# POWER.net
KiCad netlist of a schematic drawn in Altium Designer
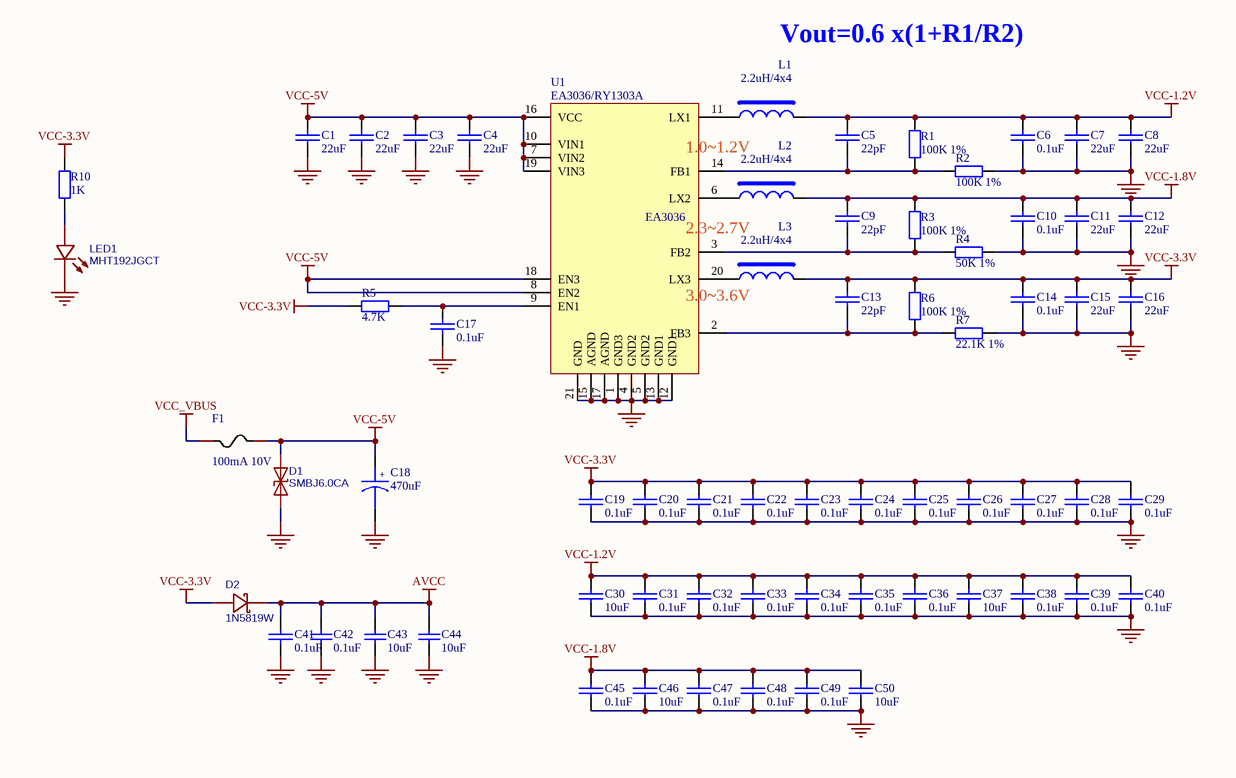
[diagram p0: POWER.SchDoc]

(export (version "E")
  (design (tool "Eeschema 10.0.6"))
  (components
    (comp (ref "C1")
      (value "22uF")
      (footprint "0805_C")
      (description "贴片电容")
      (libsource (lib "*") (part "CAP"))
    )
    (comp (ref "C2")
      (value "22uF")
      (footprint "0805_C")
      (description "贴片电容")
      (libsource (lib "*") (part "CAP"))
    )
    (comp (ref "C3")
      (value "22uF")
      (footprint "0805_C")
      (description "贴片电容")
      (libsource (lib "*") (part "CAP"))
    )
    (comp (ref "C4")
      (value "22uF")
      (footprint "0805_C")
      (description "贴片电容")
      (libsource (lib "*") (part "CAP"))
    )
    (comp (ref "C5")
      (value "22pF")
      (footprint "0402_C")
      (description "贴片电容")
      (libsource (lib "*") (part "CAP"))
    )
    (comp (ref "C6")
      (value "0.1uF")
      (footprint "0402_C")
      (description "贴片电容")
      (libsource (lib "*") (part "CAP"))
    )
    (comp (ref "C7")
      (value "22uF")
      (footprint "0805_C")
      (description "贴片电容")
      (libsource (lib "*") (part "CAP"))
    )
    (comp (ref "C8")
      (value "22uF")
      (footprint "0805_C")
      (description "贴片电容")
      (libsource (lib "*") (part "CAP"))
    )
    (comp (ref "C9")
      (value "22pF")
      (footprint "0402_C")
      (description "贴片电容")
      (libsource (lib "*") (part "CAP"))
    )
    (comp (ref "C10")
      (value "0.1uF")
      (footprint "0402_C")
      (description "贴片电容")
      (libsource (lib "*") (part "CAP"))
    )
    (comp (ref "C11")
      (value "22uF")
      (footprint "0805_C")
      (description "贴片电容")
      (libsource (lib "*") (part "CAP"))
    )
    (comp (ref "C12")
      (value "22uF")
      (footprint "0805_C")
      (description "贴片电容")
      (libsource (lib "*") (part "CAP"))
    )
    (comp (ref "C13")
      (value "22pF")
      (footprint "0402_C")
      (description "贴片电容")
      (libsource (lib "*") (part "CAP"))
    )
    (comp (ref "C14")
      (value "0.1uF")
      (footprint "0402_C")
      (description "贴片电容")
      (libsource (lib "*") (part "CAP"))
    )
    (comp (ref "C15")
      (value "22uF")
      (footprint "0805_C")
      (description "贴片电容")
      (libsource (lib "*") (part "CAP"))
    )
    (comp (ref "C16")
      (value "22uF")
      (footprint "0805_C")
      (description "贴片电容")
      (libsource (lib "*") (part "CAP"))
    )
    (comp (ref "C17")
      (value "0.1uF")
      (footprint "0402_C")
      (description "贴片电容")
      (libsource (lib "*") (part "CAP"))
    )
    (comp (ref "C18")
      (value "470uF")
      (footprint "SEC6.3")
      (description "贴片电解电容")
      (libsource (lib "*") (part "CAPACITOR POL"))
    )
    (comp (ref "C19")
      (value "0.1uF")
      (footprint "0402_C")
      (description "贴片电容")
      (libsource (lib "*") (part "CAP"))
    )
    (comp (ref "C20")
      (value "0.1uF")
      (footprint "0402_C")
      (description "贴片电容")
      (libsource (lib "*") (part "CAP"))
    )
    (comp (ref "C21")
      (value "0.1uF")
      (footprint "0402_C")
      (description "贴片电容")
      (libsource (lib "*") (part "CAP"))
    )
    (comp (ref "C22")
      (value "0.1uF")
      (footprint "0402_C")
      (description "贴片电容")
      (libsource (lib "*") (part "CAP"))
    )
    (comp (ref "C23")
      (value "0.1uF")
      (footprint "0402_C")
      (description "贴片电容")
      (libsource (lib "*") (part "CAP"))
    )
    (comp (ref "C24")
      (value "0.1uF")
      (footprint "0402_C")
      (description "贴片电容")
      (libsource (lib "*") (part "CAP"))
    )
    (comp (ref "C25")
      (value "0.1uF")
      (footprint "0402_C")
      (description "贴片电容")
      (libsource (lib "*") (part "CAP"))
    )
    (comp (ref "C26")
      (value "0.1uF")
      (footprint "0402_C")
      (description "贴片电容")
      (libsource (lib "*") (part "CAP"))
    )
    (comp (ref "C27")
      (value "0.1uF")
      (footprint "0402_C")
      (description "贴片电容")
      (libsource (lib "*") (part "CAP"))
    )
    (comp (ref "C28")
      (value "0.1uF")
      (footprint "0402_C")
      (description "贴片电容")
      (libsource (lib "*") (part "CAP"))
    )
    (comp (ref "C29")
      (value "0.1uF")
      (footprint "0402_C")
      (description "贴片电容")
      (libsource (lib "*") (part "CAP"))
    )
    (comp (ref "C30")
      (value "10uF")
      (footprint "0603_C")
      (description "贴片电容")
      (libsource (lib "*") (part "CAP"))
    )
    (comp (ref "C31")
      (value "0.1uF")
      (footprint "0402_C")
      (description "贴片电容")
      (libsource (lib "*") (part "CAP"))
    )
    (comp (ref "C32")
      (value "0.1uF")
      (footprint "0402_C")
      (description "贴片电容")
      (libsource (lib "*") (part "CAP"))
    )
    (comp (ref "C33")
      (value "0.1uF")
      (footprint "0402_C")
      (description "贴片电容")
      (libsource (lib "*") (part "CAP"))
    )
    (comp (ref "C34")
      (value "0.1uF")
      (footprint "0402_C")
      (description "贴片电容")
      (libsource (lib "*") (part "CAP"))
    )
    (comp (ref "C35")
      (value "0.1uF")
      (footprint "0402_C")
      (description "贴片电容")
      (libsource (lib "*") (part "CAP"))
    )
    (comp (ref "C36")
      (value "0.1uF")
      (footprint "0402_C")
      (description "贴片电容")
      (libsource (lib "*") (part "CAP"))
    )
    (comp (ref "C37")
      (value "10uF")
      (footprint "0603_C")
      (description "贴片电容")
      (libsource (lib "*") (part "CAP"))
    )
    (comp (ref "C38")
      (value "0.1uF")
      (footprint "0402_C")
      (description "贴片电容")
      (libsource (lib "*") (part "CAP"))
    )
    (comp (ref "C39")
      (value "0.1uF")
      (footprint "0402_C")
      (description "贴片电容")
      (libsource (lib "*") (part "CAP"))
    )
    (comp (ref "C40")
      (value "0.1uF")
      (footprint "0402_C")
      (description "贴片电容")
      (libsource (lib "*") (part "CAP"))
    )
    (comp (ref "C41")
      (value "0.1uF")
      (footprint "0402_C")
      (description "贴片电容")
      (libsource (lib "*") (part "CAP"))
    )
    (comp (ref "C42")
      (value "0.1uF")
      (footprint "0402_C")
      (description "贴片电容")
      (libsource (lib "LSD") (part "CAP-SMD"))
    )
    (comp (ref "C43")
      (value "10uF")
      (footprint "0603_C")
      (description "贴片电容")
      (libsource (lib "LSD") (part "CAP-SMD"))
    )
    (comp (ref "C44")
      (value "10uF")
      (footprint "0603_C")
      (description "贴片电容")
      (libsource (lib "LSD") (part "CAP-SMD"))
    )
    (comp (ref "C45")
      (value "0.1uF")
      (footprint "0402_C")
      (description "贴片电容")
      (libsource (lib "*") (part "CAP"))
    )
    (comp (ref "C46")
      (value "10uF")
      (footprint "0603_C")
      (description "贴片电容")
      (libsource (lib "*") (part "CAP"))
    )
    (comp (ref "C47")
      (value "0.1uF")
      (footprint "0402_C")
      (description "贴片电容")
      (libsource (lib "*") (part "CAP"))
    )
    (comp (ref "C48")
      (value "0.1uF")
      (footprint "0402_C")
      (description "贴片电容")
      (libsource (lib "*") (part "CAP"))
    )
    (comp (ref "C49")
      (value "0.1uF")
      (footprint "0402_C")
      (description "贴片电容")
      (libsource (lib "*") (part "CAP"))
    )
    (comp (ref "C50")
      (value "10uF")
      (footprint "0603_C")
      (description "贴片电容")
      (libsource (lib "*") (part "CAP"))
    )
    (comp (ref "D1")
      (value "SMBJ6.0CA")
      (footprint "SMB(DO-214AA)")
      (fields (field (name "BOM_SUPPLIER PART") "C211762") (field (name "CONTRIBUTOR") "LCSC"))
      (libsource (lib "altium-import") (part "root_1_mirrored_SMBJ6.0CA_C211762_"))
    )
    (comp (ref "D2")
      (value "1N5819W")
      (footprint "PCB_library:SOD-123")
      (description "C727115")
      (fields (field (name "CONTRIBUTOR") "LCSC"))
      (libsource (lib "altium-import") (part "root_2_1N5819W_C727115_"))
    )
    (comp (ref "F1")
      (value "100mA 10V")
      (footprint "1206_F")
      (description "贴片自恢复保险丝")
      (libsource (lib "DS32F4+A7-0501") (part "nSMD025"))
    )
    (comp (ref "L1")
      (value "2.2uH/4x4")
      (description "贴片功率电感")
      (fields (field (name "TOLERANCE") "20%") (field (name "CREATED BY") "YTL"))
      (libsource (lib "*") (part "ind1"))
    )
    (comp (ref "L2")
      (value "2.2uH/4x4")
      (description "贴片功率电感")
      (fields (field (name "TOLERANCE") "20%") (field (name "CREATED BY") "YTL"))
      (libsource (lib "*") (part "ind1"))
    )
    (comp (ref "L3")
      (value "2.2uH/4x4")
      (description "贴片功率电感")
      (fields (field (name "TOLERANCE") "20%") (field (name "CREATED BY") "YTL"))
      (libsource (lib "*") (part "ind1"))
    )
    (comp (ref "LED1")
      (value "MHT192JGCT")
      (footprint "LED0603")
      (description "LED贴片0603高亮黄绿色光,C473820")
      (fields (field (name "BOM_SUPPLIER PART") "C473820") (field (name "CONTRIBUTOR") "LCSC"))
      (libsource (lib "altium-import") (part "root_1_mirrored_MHT192JGCT_"))
    )
    (comp (ref "R1")
      (value "100K 1%")
      (footprint "0402_R")
      (description "贴片电阻")
      (libsource (lib "") (part "Res2_1"))
    )
    (comp (ref "R2")
      (value "100K 1%")
      (footprint "0402_R")
      (description "贴片电阻")
      (libsource (lib "*") (part "Res2"))
    )
    (comp (ref "R3")
      (value "100K 1%")
      (footprint "0402_R")
      (description "贴片电阻")
      (libsource (lib "") (part "Res2_1"))
    )
    (comp (ref "R4")
      (value "50K 1%")
      (footprint "0402_R")
      (description "贴片电阻")
      (libsource (lib "*") (part "Res2"))
    )
    (comp (ref "R5")
      (value "4.7K")
      (footprint "0402_R")
      (description "贴片电阻")
      (libsource (lib "") (part "Res2_1"))
    )
    (comp (ref "R6")
      (value "100K 1%")
      (footprint "0402_R")
      (description "贴片电阻")
      (libsource (lib "") (part "Res2_1"))
    )
    (comp (ref "R7")
      (value "22.1K 1%")
      (footprint "0402_R")
      (description "贴片电阻")
      (libsource (lib "*") (part "Res2"))
    )
    (comp (ref "R10")
      (value "1K")
      (footprint "0402_R")
      (description "贴片电阻")
      (libsource (lib "*") (part "Res2"))
    )
    (comp (ref "U1")
      (value "EA3036/RY1303A")
      (footprint "QFN3x3-20")
      (libsource (lib "SSD20x V1.0") (part "EA3036"))
    )
  )
  (nets
    (net (code "1") (name "AVCC") (class "Default")
      (node (ref "C41") (pin "2") (pintype "passive"))
      (node (ref "C42") (pin "1") (pintype "passive"))
      (node (ref "C43") (pin "2") (pintype "passive"))
      (node (ref "C44") (pin "2") (pintype "passive"))
      (node (ref "D2") (pin "1") (pinfunction "C_1") (pintype "passive"))
    )
    (net (code "2") (name "GND") (class "Default")
      (node (ref "C1") (pin "2") (pintype "passive"))
      (node (ref "C10") (pin "1") (pintype "passive"))
      (node (ref "C11") (pin "2") (pintype "passive"))
      (node (ref "C12") (pin "2") (pintype "passive"))
      (node (ref "C14") (pin "1") (pintype "passive"))
      (node (ref "C15") (pin "2") (pintype "passive"))
      (node (ref "C16") (pin "2") (pintype "passive"))
      (node (ref "C17") (pin "1") (pintype "passive"))
      (node (ref "C18") (pin "2") (pinfunction "2_2") (pintype "passive"))
      (node (ref "C19") (pin "1") (pintype "passive"))
      (node (ref "C2") (pin "2") (pintype "passive"))
      (node (ref "C20") (pin "1") (pintype "passive"))
      (node (ref "C21") (pin "1") (pintype "passive"))
      (node (ref "C22") (pin "1") (pintype "passive"))
      (node (ref "C23") (pin "1") (pintype "passive"))
      (node (ref "C24") (pin "1") (pintype "passive"))
      (node (ref "C25") (pin "1") (pintype "passive"))
      (node (ref "C26") (pin "1") (pintype "passive"))
      (node (ref "C27") (pin "1") (pintype "passive"))
      (node (ref "C28") (pin "1") (pintype "passive"))
      (node (ref "C29") (pin "1") (pintype "passive"))
      (node (ref "C3") (pin "2") (pintype "passive"))
      (node (ref "C30") (pin "1") (pintype "passive"))
      (node (ref "C31") (pin "1") (pintype "passive"))
      (node (ref "C32") (pin "1") (pintype "passive"))
      (node (ref "C33") (pin "1") (pintype "passive"))
      (node (ref "C34") (pin "1") (pintype "passive"))
      (node (ref "C35") (pin "1") (pintype "passive"))
      (node (ref "C36") (pin "1") (pintype "passive"))
      (node (ref "C37") (pin "1") (pintype "passive"))
      (node (ref "C38") (pin "1") (pintype "passive"))
      (node (ref "C39") (pin "1") (pintype "passive"))
      (node (ref "C4") (pin "2") (pintype "passive"))
      (node (ref "C40") (pin "1") (pintype "passive"))
      (node (ref "C41") (pin "1") (pintype "passive"))
      (node (ref "C42") (pin "2") (pintype "passive"))
      (node (ref "C43") (pin "1") (pintype "passive"))
      (node (ref "C44") (pin "1") (pintype "passive"))
      (node (ref "C45") (pin "1") (pintype "passive"))
      (node (ref "C46") (pin "1") (pintype "passive"))
      (node (ref "C47") (pin "1") (pintype "passive"))
      (node (ref "C48") (pin "1") (pintype "passive"))
      (node (ref "C49") (pin "1") (pintype "passive"))
      (node (ref "C50") (pin "1") (pintype "passive"))
      (node (ref "C6") (pin "1") (pintype "passive"))
      (node (ref "C7") (pin "2") (pintype "passive"))
      (node (ref "C8") (pin "2") (pintype "passive"))
      (node (ref "D1") (pin "2") (pinfunction "A1_2") (pintype "passive"))
      (node (ref "LED1") (pin "1") (pinfunction "-_1") (pintype "passive"))
      (node (ref "R2") (pin "2") (pinfunction "2_2") (pintype "passive"))
      (node (ref "R4") (pin "2") (pinfunction "2_2") (pintype "passive"))
      (node (ref "R7") (pin "2") (pinfunction "2_2") (pintype "passive"))
      (node (ref "U1") (pin "1") (pinfunction "GND3_1") (pintype "passive"))
      (node (ref "U1") (pin "12") (pinfunction "GND1_12") (pintype "passive"))
      (node (ref "U1") (pin "13") (pinfunction "GND1_13") (pintype "passive"))
      (node (ref "U1") (pin "15") (pinfunction "AGND_15") (pintype "passive"))
      (node (ref "U1") (pin "17") (pinfunction "AGND_17") (pintype "passive"))
      (node (ref "U1") (pin "21") (pinfunction "GND_21") (pintype "passive"))
      (node (ref "U1") (pin "4") (pinfunction "GND2_4") (pintype "passive"))
      (node (ref "U1") (pin "5") (pinfunction "GND2_5") (pintype "passive"))
    )
    (net (code "3") (name "Net-(LED1-+)") (class "Default")
      (node (ref "LED1") (pin "2") (pinfunction "+_2") (pintype "passive"))
      (node (ref "R10") (pin "1") (pinfunction "1_1") (pintype "passive"))
    )
    (net (code "4") (name "Net-(U1-EN1)") (class "Default")
      (node (ref "C17") (pin "2") (pintype "passive"))
      (node (ref "R5") (pin "2") (pinfunction "2_2") (pintype "passive"))
      (node (ref "U1") (pin "9") (pinfunction "EN1_9") (pintype "passive"))
    )
    (net (code "5") (name "Net-(U1-FB1)") (class "Default")
      (node (ref "C5") (pin "1") (pintype "passive"))
      (node (ref "R1") (pin "1") (pinfunction "1_1") (pintype "passive"))
      (node (ref "R2") (pin "1") (pinfunction "1_1") (pintype "passive"))
      (node (ref "U1") (pin "14") (pinfunction "FB1_14") (pintype "passive"))
    )
    (net (code "6") (name "Net-(U1-FB2)") (class "Default")
      (node (ref "C9") (pin "1") (pintype "passive"))
      (node (ref "R3") (pin "1") (pinfunction "1_1") (pintype "passive"))
      (node (ref "R4") (pin "1") (pinfunction "1_1") (pintype "passive"))
      (node (ref "U1") (pin "3") (pinfunction "FB2_3") (pintype "passive"))
    )
    (net (code "7") (name "Net-(U1-FB3)") (class "Default")
      (node (ref "C13") (pin "1") (pintype "passive"))
      (node (ref "R6") (pin "1") (pinfunction "1_1") (pintype "passive"))
      (node (ref "R7") (pin "1") (pinfunction "1_1") (pintype "passive"))
      (node (ref "U1") (pin "2") (pinfunction "FB3_2") (pintype "passive"))
    )
    (net (code "8") (name "Net-(U1-LX1)") (class "Default")
      (node (ref "L1") (pin "2") (pinfunction "2_2") (pintype "passive"))
      (node (ref "U1") (pin "11") (pinfunction "LX1_11") (pintype "passive"))
    )
    (net (code "9") (name "Net-(U1-LX2)") (class "Default")
      (node (ref "L2") (pin "2") (pinfunction "2_2") (pintype "passive"))
      (node (ref "U1") (pin "6") (pinfunction "LX2_6") (pintype "passive"))
    )
    (net (code "10") (name "Net-(U1-LX3)") (class "Default")
      (node (ref "L3") (pin "2") (pinfunction "2_2") (pintype "passive"))
      (node (ref "U1") (pin "20") (pinfunction "LX3_20") (pintype "passive"))
    )
    (net (code "11") (name "VCC-1.2V") (class "Default")
      (node (ref "C30") (pin "2") (pintype "passive"))
      (node (ref "C31") (pin "2") (pintype "passive"))
      (node (ref "C32") (pin "2") (pintype "passive"))
      (node (ref "C33") (pin "2") (pintype "passive"))
      (node (ref "C34") (pin "2") (pintype "passive"))
      (node (ref "C35") (pin "2") (pintype "passive"))
      (node (ref "C36") (pin "2") (pintype "passive"))
      (node (ref "C37") (pin "2") (pintype "passive"))
      (node (ref "C38") (pin "2") (pintype "passive"))
      (node (ref "C39") (pin "2") (pintype "passive"))
      (node (ref "C40") (pin "2") (pintype "passive"))
      (node (ref "C5") (pin "2") (pintype "passive"))
      (node (ref "C6") (pin "2") (pintype "passive"))
      (node (ref "C7") (pin "1") (pintype "passive"))
      (node (ref "C8") (pin "1") (pintype "passive"))
      (node (ref "L1") (pin "1") (pinfunction "1_1") (pintype "passive"))
      (node (ref "R1") (pin "2") (pinfunction "2_2") (pintype "passive"))
    )
    (net (code "12") (name "VCC-1.8V") (class "Default")
      (node (ref "C10") (pin "2") (pintype "passive"))
      (node (ref "C11") (pin "1") (pintype "passive"))
      (node (ref "C12") (pin "1") (pintype "passive"))
      (node (ref "C45") (pin "2") (pintype "passive"))
      (node (ref "C46") (pin "2") (pintype "passive"))
      (node (ref "C47") (pin "2") (pintype "passive"))
      (node (ref "C48") (pin "2") (pintype "passive"))
      (node (ref "C49") (pin "2") (pintype "passive"))
      (node (ref "C50") (pin "2") (pintype "passive"))
      (node (ref "C9") (pin "2") (pintype "passive"))
      (node (ref "L2") (pin "1") (pinfunction "1_1") (pintype "passive"))
      (node (ref "R3") (pin "2") (pinfunction "2_2") (pintype "passive"))
    )
    (net (code "13") (name "VCC-3.3V") (class "Default")
      (node (ref "C13") (pin "2") (pintype "passive"))
      (node (ref "C14") (pin "2") (pintype "passive"))
      (node (ref "C15") (pin "1") (pintype "passive"))
      (node (ref "C16") (pin "1") (pintype "passive"))
      (node (ref "C19") (pin "2") (pintype "passive"))
      (node (ref "C20") (pin "2") (pintype "passive"))
      (node (ref "C21") (pin "2") (pintype "passive"))
      (node (ref "C22") (pin "2") (pintype "passive"))
      (node (ref "C23") (pin "2") (pintype "passive"))
      (node (ref "C24") (pin "2") (pintype "passive"))
      (node (ref "C25") (pin "2") (pintype "passive"))
      (node (ref "C26") (pin "2") (pintype "passive"))
      (node (ref "C27") (pin "2") (pintype "passive"))
      (node (ref "C28") (pin "2") (pintype "passive"))
      (node (ref "C29") (pin "2") (pintype "passive"))
      (node (ref "D2") (pin "2") (pinfunction "A_2") (pintype "passive"))
      (node (ref "L3") (pin "1") (pinfunction "1_1") (pintype "passive"))
      (node (ref "R10") (pin "2") (pinfunction "2_2") (pintype "passive"))
      (node (ref "R5") (pin "1") (pinfunction "1_1") (pintype "passive"))
      (node (ref "R6") (pin "2") (pinfunction "2_2") (pintype "passive"))
    )
    (net (code "14") (name "VCC-5V") (class "Default")
      (node (ref "C1") (pin "1") (pintype "passive"))
      (node (ref "C18") (pin "1") (pinfunction "1_1") (pintype "passive"))
      (node (ref "C2") (pin "1") (pintype "passive"))
      (node (ref "C3") (pin "1") (pintype "passive"))
      (node (ref "C4") (pin "1") (pintype "passive"))
      (node (ref "D1") (pin "1") (pinfunction "A2_1") (pintype "passive"))
      (node (ref "F1") (pin "1") (pinfunction "1_1") (pintype "passive"))
      (node (ref "U1") (pin "10") (pinfunction "VIN1_10") (pintype "passive"))
      (node (ref "U1") (pin "16") (pinfunction "VCC_16") (pintype "passive"))
      (node (ref "U1") (pin "18") (pinfunction "EN3_18") (pintype "passive"))
      (node (ref "U1") (pin "19") (pinfunction "VIN3_19") (pintype "passive"))
      (node (ref "U1") (pin "7") (pinfunction "VIN2_7") (pintype "passive"))
      (node (ref "U1") (pin "8") (pinfunction "EN2_8") (pintype "passive"))
    )
    (net (code "15") (name "VCC_VBUS") (class "Default")
      (node (ref "F1") (pin "2") (pinfunction "2_2") (pintype "passive"))
    )
  )
)
